# Lipo_LiFePO4_Charger_2022-02-16.net
KiCad netlist of a schematic drawn in Altium Designer
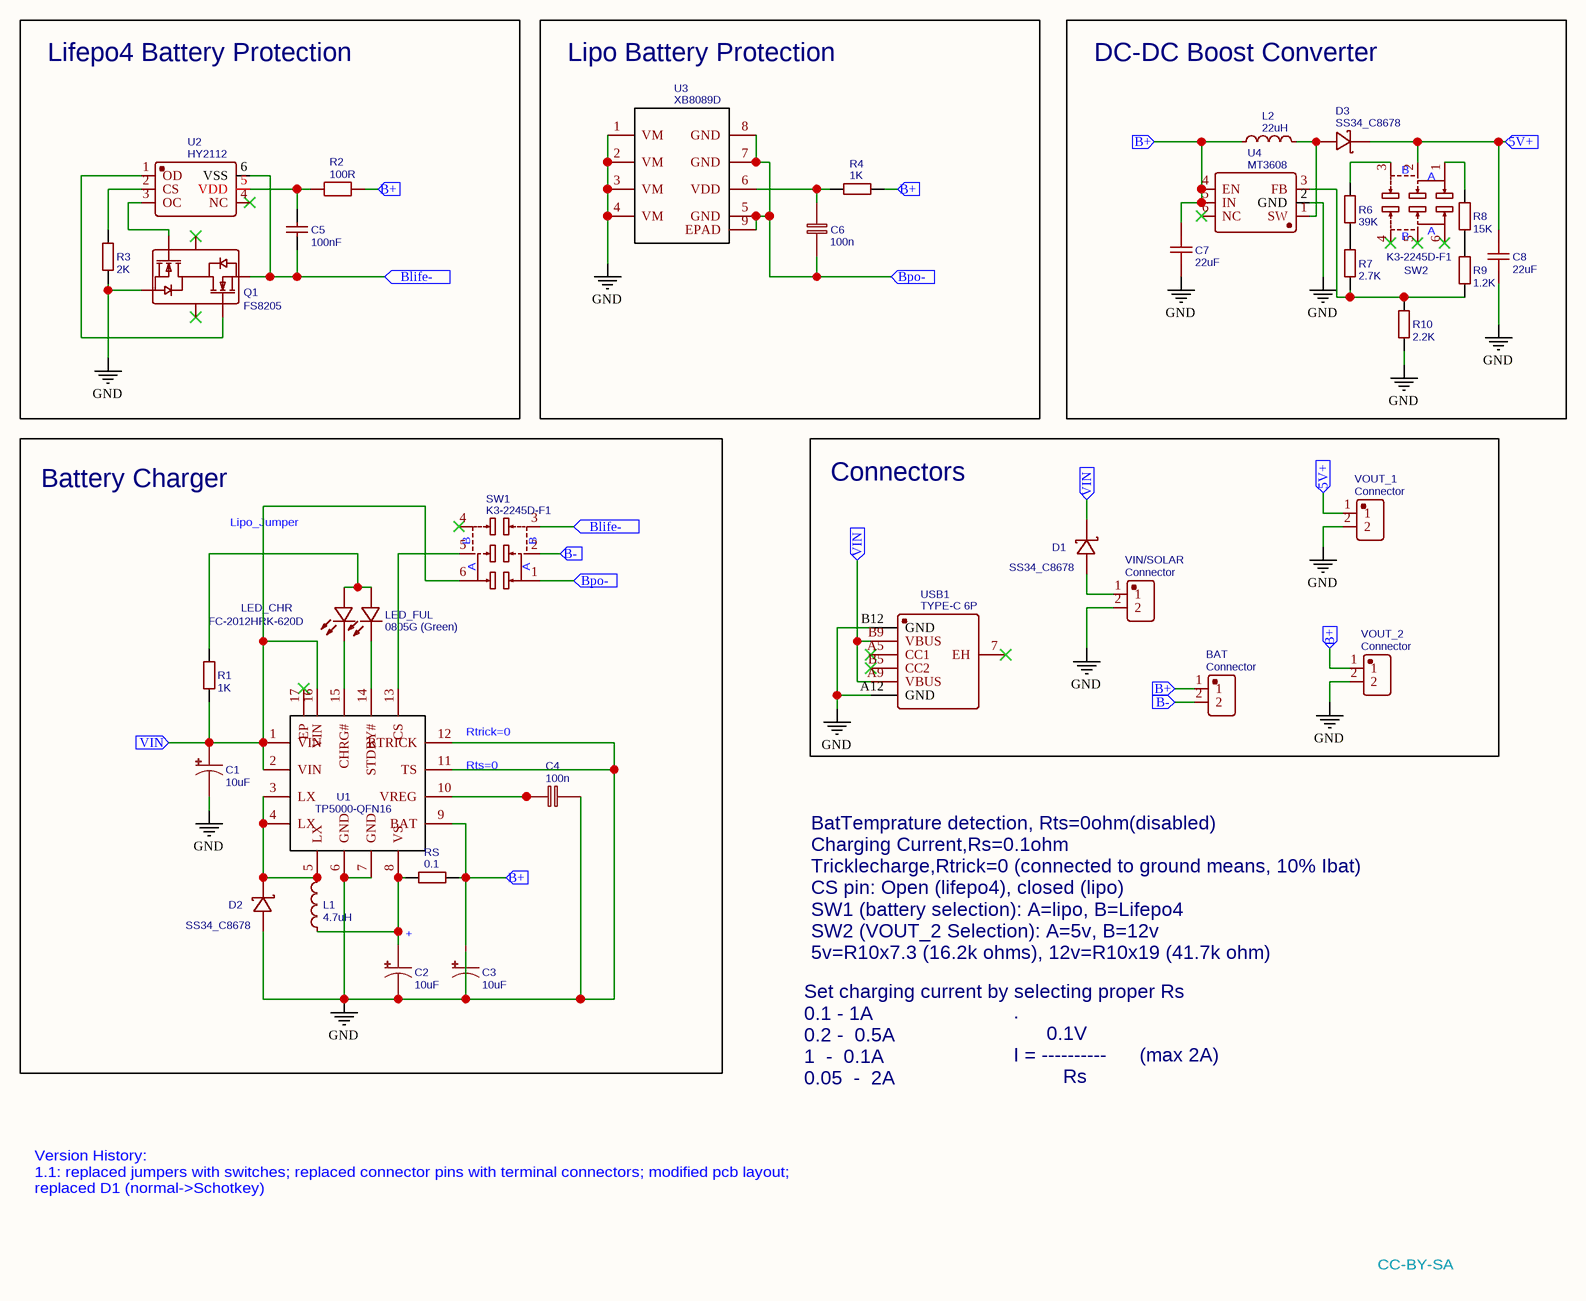
[diagram p0: Lipo_LiFePO4 Charger_2022-02-16.schdoc]

(export (version "E")
  (design (tool "Eeschema 10.0.6"))
  (components
    (comp (ref "BAT")
      (value "Connector")
      (fields
        (field (name "BOM_SUPPLIER PART") "C557685")
        (field (name "BOM_MANUFACTURER PART") "XY308-2.54-2P")
        (field (name "CONTRIBUTOR") "LCSC")
      )
      (libsource (lib "altium-import") (part "root_0_Connector_"))
    )
    (comp (ref "C1")
      (value "10uF")
      (fields
        (field (name "BOM_MANUFACTURER PART") "293D106X9020B2TE3")
        (field (name "BOM_SUPPLIER PART") "C180482")
        (field (name "CONTRIBUTOR") "LCSC")
      )
      (libsource (lib "altium-import") (part "root_1_10uF_"))
    )
    (comp (ref "C2")
      (value "10uF")
      (fields
        (field (name "BOM_MANUFACTURER PART") "293D106X9020B2TE3")
        (field (name "BOM_SUPPLIER PART") "C180482")
        (field (name "CONTRIBUTOR") "LCSC")
      )
      (libsource (lib "altium-import") (part "root_1_10uF_"))
    )
    (comp (ref "C3")
      (value "10uF")
      (fields
        (field (name "BOM_MANUFACTURER PART") "293D106X9020B2TE3")
        (field (name "BOM_SUPPLIER PART") "C180482")
        (field (name "CONTRIBUTOR") "LCSC")
      )
      (libsource (lib "altium-import") (part "root_1_10uF_"))
    )
    (comp (ref "C4")
      (value "100n")
      (fields
        (field (name "BOM_MANUFACTURER PART") "CC0805KRX7R9BB104")
        (field (name "BOM_SUPPLIER PART") "C49678")
      )
      (libsource (lib "altium-import") (part "root_1_100n_"))
    )
    (comp (ref "C5")
      (value "100nF")
      (fields
        (field (name "BOM_MANUFACTURER PART") "CC0805KRX7R9BB104")
        (field (name "BOM_SUPPLIER PART") "C49678")
      )
      (libsource (lib "altium-import") (part "root_1_100nF_"))
    )
    (comp (ref "C6")
      (value "100n")
      (fields
        (field (name "BOM_MANUFACTURER PART") "CC0805KRX7R9BB104")
        (field (name "BOM_SUPPLIER PART") "C49678")
      )
      (libsource (lib "altium-import") (part "root_0_100n_"))
    )
    (comp (ref "C7")
      (value "22uF")
      (fields
        (field (name "BOM_MANUFACTURER PART") "CL21A226MAQNNNE")
        (field (name "BOM_SUPPLIER PART") "C45783")
      )
      (libsource (lib "altium-import") (part "root_1_22uF_"))
    )
    (comp (ref "C8")
      (value "22uF")
      (fields
        (field (name "BOM_MANUFACTURER PART") "CL21A226MAQNNNE")
        (field (name "BOM_SUPPLIER PART") "C45783")
      )
      (libsource (lib "altium-import") (part "root_1_22uF_"))
    )
    (comp (ref "D1")
      (value "SS34_C8678")
      (fields (field (name "BOM_MANUFACTURER PART") "SS34") (field (name "BOM_SUPPLIER PART") "C8678"))
      (libsource (lib "altium-import") (part "root_3_SS34_C8678_"))
    )
    (comp (ref "D2")
      (value "SS34_C8678")
      (fields (field (name "BOM_MANUFACTURER PART") "SS34") (field (name "BOM_SUPPLIER PART") "C8678"))
      (libsource (lib "altium-import") (part "root_3_SS34_C8678_"))
    )
    (comp (ref "D3")
      (value "SS34_C8678")
      (fields (field (name "BOM_MANUFACTURER PART") "SS34") (field (name "BOM_SUPPLIER PART") "C8678"))
      (libsource (lib "altium-import") (part "root_2_SS34_C8678_"))
    )
    (comp (ref "L1")
      (value "4.7uH")
      (fields
        (field (name "BOM_MANUFACTURER PART") "SMMS0650-4R7M")
        (field (name "BOM_SUPPLIER PART") "C149582")
      )
      (libsource (lib "altium-import") (part "root_1_4.7uH_"))
    )
    (comp (ref "L2")
      (value "22uH")
      (fields
        (field (name "BOM_MANUFACTURER PART") "SMRH74-220MT")
        (field (name "BOM_SUPPLIER PART") "C27442")
      )
      (libsource (lib "altium-import") (part "root_0_22uH_"))
    )
    (comp (ref "LED_CHR")
      (value "FC-2012HRK-620D")
      (fields (field (name "BOM_SUPPLIER PART") "C84256"))
      (libsource (lib "altium-import") (part "root_1_FC-2012HRK-620D_"))
    )
    (comp (ref "LED_FUL")
      (value "0805G (Green)")
      (fields (field (name "BOM_SUPPLIER PART") "C2297"))
      (libsource (lib "altium-import") (part "root_1_0805G (Green)_"))
    )
    (comp (ref "Q1")
      (value "FS8205")
      (fields (field (name "BOM_SUPPLIER PART") "C32254"))
      (libsource (lib "altium-import") (part "root_2_FS8205_"))
    )
    (comp (ref "R1")
      (value "1K")
      (fields
        (field (name "BOM_MANUFACTURER PART") "0805W8F1001T5E")
        (field (name "BOM_SUPPLIER PART") "C17513")
      )
      (libsource (lib "altium-import") (part "root_1_1K_"))
    )
    (comp (ref "R2")
      (value "100R")
      (fields
        (field (name "BOM_MANUFACTURER PART") "0805W8F1000T5E")
        (field (name "BOM_SUPPLIER PART") "C17408")
      )
      (libsource (lib "altium-import") (part "root_0_100R_"))
    )
    (comp (ref "R3")
      (value "2K")
      (fields
        (field (name "BOM_MANUFACTURER PART") "0805W8F2001T5E")
        (field (name "BOM_SUPPLIER PART") "C17604")
      )
      (libsource (lib "altium-import") (part "root_1_2K_"))
    )
    (comp (ref "R4")
      (value "1K")
      (fields
        (field (name "BOM_MANUFACTURER PART") "0805W8F1001T5E")
        (field (name "BOM_SUPPLIER PART") "C17513")
      )
      (libsource (lib "altium-import") (part "root_2_1K_"))
    )
    (comp (ref "R6")
      (value "39K")
      (fields
        (field (name "BOM_MANUFACTURER PART") "0805W8F3902T5E")
        (field (name "BOM_SUPPLIER PART") "C25826")
      )
      (libsource (lib "altium-import") (part "root_1_39K_"))
    )
    (comp (ref "R7")
      (value "2.7K")
      (fields
        (field (name "BOM_MANUFACTURER PART") "0805W8F2701T5E")
        (field (name "BOM_SUPPLIER PART") "C17530")
      )
      (libsource (lib "altium-import") (part "root_1_2.7K_"))
    )
    (comp (ref "R8")
      (value "15K")
      (fields
        (field (name "BOM_MANUFACTURER PART") "0805W8F1502T5E")
        (field (name "BOM_SUPPLIER PART") "C17475")
      )
      (libsource (lib "altium-import") (part "root_1_15K_"))
    )
    (comp (ref "R9")
      (value "1.2K")
      (fields
        (field (name "BOM_MANUFACTURER PART") "0805W8F1201T5E")
        (field (name "BOM_SUPPLIER PART") "C17379")
      )
      (libsource (lib "altium-import") (part "root_1_1.2K_"))
    )
    (comp (ref "R10")
      (value "2.2K")
      (fields
        (field (name "BOM_MANUFACTURER PART") "0805W8F2201T5E")
        (field (name "BOM_SUPPLIER PART") "C17520")
      )
      (libsource (lib "altium-import") (part "root_1_2.2K_"))
    )
    (comp (ref "RS")
      (value "0.1")
      (fields
        (field (name "BOM_MANUFACTURER PART") "1206W4F100LT5E")
        (field (name "BOM_SUPPLIER PART") "C25334")
      )
      (libsource (lib "altium-import") (part "root_0_0.1_"))
    )
    (comp (ref "SW1")
      (value "K3-2245D-F1")
      (fields (field (name "BOM_SUPPLIER PART") "C223863") (field (name "CONTRIBUTOR") "LCSC"))
      (libsource (lib "altium-import") (part "root_1_K3-2245D-F1_"))
    )
    (comp (ref "SW2")
      (value "K3-2245D-F1")
      (fields (field (name "BOM_SUPPLIER PART") "C223863") (field (name "CONTRIBUTOR") "LCSC"))
      (libsource (lib "altium-import") (part "root_2_K3-2245D-F1_"))
    )
    (comp (ref "U1")
      (value "TP5000-QFN16")
      (fields (field (name "BOM_SUPPLIER PART") "C51699"))
      (libsource (lib "altium-import") (part "root_0_TP5000-QFN16_"))
    )
    (comp (ref "U2")
      (value "HY2112")
      (fields (field (name "BOM_SUPPLIER PART") "C161942") (field (name "CONTRIBUTOR") "LCSC"))
      (libsource (lib "altium-import") (part "root_0_HY2112_"))
    )
    (comp (ref "U3")
      (value "XB8089D")
      (fields (field (name "BOM_SUPPLIER PART") "C79928"))
      (libsource (lib "altium-import") (part "root_0_XB8089D_"))
    )
    (comp (ref "U4")
      (value "MT3608")
      (fields (field (name "BOM_SUPPLIER PART") "C84817"))
      (libsource (lib "altium-import") (part "root_2_MT3608_"))
    )
    (comp (ref "USB1")
      (value "TYPE-C 6P")
      (fields (field (name "BOM_SUPPLIER PART") "C456012") (field (name "CONTRIBUTOR") "LCSC"))
      (libsource (lib "altium-import") (part "root_0_TYPE-C 6P_"))
    )
    (comp (ref "VIN/SOLAR")
      (value "Connector")
      (fields
        (field (name "BOM_SUPPLIER PART") "C557685")
        (field (name "BOM_MANUFACTURER PART") "XY308-2.54-2P")
        (field (name "CONTRIBUTOR") "LCSC")
      )
      (libsource (lib "altium-import") (part "root_0_Connector_"))
    )
    (comp (ref "VOUT_1")
      (value "Connector")
      (fields
        (field (name "BOM_SUPPLIER PART") "C557685")
        (field (name "BOM_MANUFACTURER PART") "XY308-2.54-2P")
        (field (name "CONTRIBUTOR") "LCSC")
      )
      (libsource (lib "altium-import") (part "root_0_Connector_"))
    )
    (comp (ref "VOUT_2")
      (value "Connector")
      (fields
        (field (name "BOM_SUPPLIER PART") "C557685")
        (field (name "BOM_MANUFACTURER PART") "XY308-2.54-2P")
        (field (name "CONTRIBUTOR") "LCSC")
      )
      (libsource (lib "altium-import") (part "root_0_Connector_"))
    )
  )
  (nets
    (net (code "1") (name "/5V+") (class "Default")
      (node (ref "C8") (pin "2") (pinfunction "2_2") (pintype "passive"))
      (node (ref "D3") (pin "1") (pinfunction "K_1") (pintype "passive"))
      (node (ref "SW2") (pin "2") (pinfunction "2_2") (pintype "passive"))
      (node (ref "VOUT_1") (pin "1") (pinfunction "1_1") (pintype "passive"))
    )
    (net (code "2") (name "/B+") (class "Default")
      (node (ref "BAT") (pin "1") (pinfunction "1_1") (pintype "passive"))
      (node (ref "C3") (pin "1") (pinfunction "1_1") (pintype "passive"))
      (node (ref "C7") (pin "2") (pinfunction "2_2") (pintype "passive"))
      (node (ref "L2") (pin "1") (pinfunction "1_1") (pintype "passive"))
      (node (ref "R2") (pin "2") (pinfunction "2_2") (pintype "passive"))
      (node (ref "R4") (pin "1") (pinfunction "1_1") (pintype "passive"))
      (node (ref "RS") (pin "2") (pinfunction "2_2") (pintype "passive"))
      (node (ref "U1") (pin "9") (pinfunction "BAT_9") (pintype "passive"))
      (node (ref "U4") (pin "4") (pinfunction "EN_4") (pintype "passive"))
      (node (ref "U4") (pin "5") (pinfunction "IN_5") (pintype "passive"))
      (node (ref "VOUT_2") (pin "1") (pinfunction "1_1") (pintype "passive"))
    )
    (net (code "3") (name "/B-") (class "Default")
      (node (ref "BAT") (pin "2") (pinfunction "2_2") (pintype "passive"))
      (node (ref "SW1") (pin "2") (pinfunction "2_2") (pintype "passive"))
    )
    (net (code "4") (name "/Blife-") (class "Default")
      (node (ref "C5") (pin "1") (pinfunction "1_1") (pintype "passive"))
      (node (ref "Q1") (pin "1") (pinfunction "S1_1") (pintype "passive"))
      (node (ref "SW1") (pin "3") (pinfunction "3_3") (pintype "passive"))
      (node (ref "U2") (pin "6") (pinfunction "VSS_6") (pintype "passive"))
    )
    (net (code "5") (name "/Bpo-") (class "Default")
      (node (ref "C6") (pin "2") (pinfunction "2_2") (pintype "passive"))
      (node (ref "SW1") (pin "1") (pinfunction "1_1") (pintype "passive"))
      (node (ref "U3") (pin "5") (pinfunction "GND_5") (pintype "passive"))
      (node (ref "U3") (pin "7") (pinfunction "GND_7") (pintype "passive"))
      (node (ref "U3") (pin "8") (pinfunction "GND_8") (pintype "passive"))
      (node (ref "U3") (pin "9") (pinfunction "EPAD_9") (pintype "passive"))
    )
    (net (code "6") (name "/VIN") (class "Default")
      (node (ref "C1") (pin "1") (pinfunction "1_1") (pintype "passive"))
      (node (ref "D1") (pin "1") (pinfunction "K_1") (pintype "passive"))
      (node (ref "R1") (pin "1") (pinfunction "1_1") (pintype "passive"))
      (node (ref "SW1") (pin "6") (pinfunction "6_6") (pintype "passive"))
      (node (ref "U1") (pin "1") (pinfunction "VIN_1") (pintype "passive"))
      (node (ref "U1") (pin "16") (pinfunction "VIN_16") (pintype "passive"))
      (node (ref "U1") (pin "2") (pinfunction "VIN_2") (pintype "passive"))
      (node (ref "USB1") (pin "A9") (pinfunction "VBUS_A9") (pintype "passive"))
      (node (ref "USB1") (pin "B9") (pinfunction "VBUS_B9") (pintype "passive"))
    )
    (net (code "7") (name "GND") (class "Default")
      (node (ref "C1") (pin "2") (pinfunction "2_2") (pintype "passive"))
      (node (ref "C2") (pin "2") (pinfunction "2_2") (pintype "passive"))
      (node (ref "C3") (pin "2") (pinfunction "2_2") (pintype "passive"))
      (node (ref "C4") (pin "2") (pinfunction "2_2") (pintype "passive"))
      (node (ref "C7") (pin "1") (pinfunction "1_1") (pintype "passive"))
      (node (ref "C8") (pin "1") (pinfunction "1_1") (pintype "passive"))
      (node (ref "D2") (pin "2") (pinfunction "A_2") (pintype "passive"))
      (node (ref "Q1") (pin "3") (pinfunction "S2_3") (pintype "passive"))
      (node (ref "R10") (pin "1") (pinfunction "1_1") (pintype "passive"))
      (node (ref "R3") (pin "1") (pinfunction "1_1") (pintype "passive"))
      (node (ref "U1") (pin "11") (pinfunction "TS_11") (pintype "passive"))
      (node (ref "U1") (pin "12") (pinfunction "RTRICK_12") (pintype "passive"))
      (node (ref "U1") (pin "6") (pinfunction "GND_6") (pintype "passive"))
      (node (ref "U1") (pin "7") (pinfunction "GND_7") (pintype "passive"))
      (node (ref "U3") (pin "1") (pinfunction "VM_1") (pintype "passive"))
      (node (ref "U3") (pin "2") (pinfunction "VM_2") (pintype "passive"))
      (node (ref "U3") (pin "3") (pinfunction "VM_3") (pintype "passive"))
      (node (ref "U3") (pin "4") (pinfunction "VM_4") (pintype "passive"))
      (node (ref "U4") (pin "2") (pinfunction "GND_2") (pintype "passive"))
      (node (ref "USB1") (pin "A12") (pinfunction "GND_A12") (pintype "passive"))
      (node (ref "USB1") (pin "B12") (pinfunction "GND_B12") (pintype "passive"))
      (node (ref "VIN/SOLAR") (pin "2") (pinfunction "2_2") (pintype "passive"))
      (node (ref "VOUT_1") (pin "2") (pinfunction "2_2") (pintype "passive"))
      (node (ref "VOUT_2") (pin "2") (pinfunction "2_2") (pintype "passive"))
    )
    (net (code "8") (name "Net-(D1-A)") (class "Default")
      (node (ref "D1") (pin "2") (pinfunction "A_2") (pintype "passive"))
      (node (ref "VIN/SOLAR") (pin "1") (pinfunction "1_1") (pintype "passive"))
    )
    (net (code "9") (name "Net-(D2-K)") (class "Default")
      (node (ref "D2") (pin "1") (pinfunction "K_1") (pintype "passive"))
      (node (ref "L1") (pin "2") (pinfunction "2_2") (pintype "passive"))
      (node (ref "U1") (pin "3") (pinfunction "LX_3") (pintype "passive"))
      (node (ref "U1") (pin "4") (pinfunction "LX_4") (pintype "passive"))
      (node (ref "U1") (pin "5") (pinfunction "LX_5") (pintype "passive"))
    )
    (net (code "10") (name "Net-(D3-A)") (class "Default")
      (node (ref "D3") (pin "2") (pinfunction "A_2") (pintype "passive"))
      (node (ref "L2") (pin "2") (pinfunction "2_2") (pintype "passive"))
      (node (ref "U4") (pin "1") (pinfunction "SW_1") (pintype "passive"))
    )
    (net (code "11") (name "Net-(LED_CHR-+)") (class "Default")
      (node (ref "LED_CHR") (pin "2") (pinfunction "+_2") (pintype "passive"))
      (node (ref "LED_FUL") (pin "2") (pinfunction "A_2") (pintype "passive"))
      (node (ref "R1") (pin "2") (pinfunction "2_2") (pintype "passive"))
    )
    (net (code "12") (name "Net-(LED_CHR--)") (class "Default")
      (node (ref "LED_CHR") (pin "1") (pinfunction "-_1") (pintype "passive"))
      (node (ref "U1") (pin "15") (pinfunction "CHRG#_15") (pintype "passive"))
    )
    (net (code "13") (name "Net-(LED_FUL-K)") (class "Default")
      (node (ref "LED_FUL") (pin "1") (pinfunction "K_1") (pintype "passive"))
      (node (ref "U1") (pin "14") (pinfunction "STDBY#_14") (pintype "passive"))
    )
    (net (code "14") (name "Net-(Q1-G1)") (class "Default")
      (node (ref "Q1") (pin "6") (pinfunction "G1_6") (pintype "passive"))
      (node (ref "U2") (pin "1") (pinfunction "OD_1") (pintype "passive"))
    )
    (net (code "15") (name "Net-(Q1-G2)") (class "Default")
      (node (ref "Q1") (pin "4") (pinfunction "G2_4") (pintype "passive"))
      (node (ref "U2") (pin "3") (pinfunction "OC_3") (pintype "passive"))
    )
    (net (code "16") (name "Net-(R6-Pad1)") (class "Default")
      (node (ref "R6") (pin "1") (pinfunction "1_1") (pintype "passive"))
      (node (ref "R7") (pin "2") (pinfunction "2_2") (pintype "passive"))
    )
    (net (code "17") (name "Net-(R6-Pad2)") (class "Default")
      (node (ref "R6") (pin "2") (pinfunction "2_2") (pintype "passive"))
      (node (ref "SW2") (pin "3") (pinfunction "3_3") (pintype "passive"))
    )
    (net (code "18") (name "Net-(R8-Pad1)") (class "Default")
      (node (ref "R8") (pin "1") (pinfunction "1_1") (pintype "passive"))
      (node (ref "R9") (pin "2") (pinfunction "2_2") (pintype "passive"))
    )
    (net (code "19") (name "Net-(R8-Pad2)") (class "Default")
      (node (ref "R8") (pin "2") (pinfunction "2_2") (pintype "passive"))
      (node (ref "SW2") (pin "1") (pinfunction "1_1") (pintype "passive"))
    )
    (net (code "20") (name "Net-(U1-CS)") (class "Default")
      (node (ref "SW1") (pin "5") (pinfunction "5_5") (pintype "passive"))
      (node (ref "U1") (pin "13") (pinfunction "CS_13") (pintype "passive"))
    )
    (net (code "21") (name "Net-(U1-VREG)") (class "Default")
      (node (ref "C4") (pin "1") (pinfunction "1_1") (pintype "passive"))
      (node (ref "U1") (pin "10") (pinfunction "VREG_10") (pintype "passive"))
    )
    (net (code "22") (name "Net-(U1-VS)") (class "Default")
      (node (ref "C2") (pin "1") (pinfunction "1_1") (pintype "passive"))
      (node (ref "L1") (pin "1") (pinfunction "1_1") (pintype "passive"))
      (node (ref "RS") (pin "1") (pinfunction "1_1") (pintype "passive"))
      (node (ref "U1") (pin "8") (pinfunction "VS_8") (pintype "passive"))
    )
    (net (code "23") (name "Net-(U2-CS)") (class "Default")
      (node (ref "R3") (pin "2") (pinfunction "2_2") (pintype "passive"))
      (node (ref "U2") (pin "2") (pinfunction "CS_2") (pintype "passive"))
    )
    (net (code "24") (name "Net-(U2-VDD)") (class "Default")
      (node (ref "C5") (pin "2") (pinfunction "2_2") (pintype "passive"))
      (node (ref "R2") (pin "1") (pinfunction "1_1") (pintype "passive"))
      (node (ref "U2") (pin "5") (pinfunction "VDD_5") (pintype "passive"))
    )
    (net (code "25") (name "Net-(U3-VDD)") (class "Default")
      (node (ref "C6") (pin "1") (pinfunction "1_1") (pintype "passive"))
      (node (ref "R4") (pin "2") (pinfunction "2_2") (pintype "passive"))
      (node (ref "U3") (pin "6") (pinfunction "VDD_6") (pintype "passive"))
    )
    (net (code "26") (name "Net-(U4-FB)") (class "Default")
      (node (ref "R10") (pin "2") (pinfunction "2_2") (pintype "passive"))
      (node (ref "R7") (pin "1") (pinfunction "1_1") (pintype "passive"))
      (node (ref "R9") (pin "1") (pinfunction "1_1") (pintype "passive"))
      (node (ref "U4") (pin "3") (pinfunction "FB_3") (pintype "passive"))
    )
    (net (code "27") (name "unconnected-(Q1-D12-Pad2)") (class "Default")
      (node (ref "Q1") (pin "2") (pinfunction "D12_2") (pintype "passive+no_connect"))
    )
    (net (code "28") (name "unconnected-(Q1-D12-Pad5)") (class "Default")
      (node (ref "Q1") (pin "5") (pinfunction "D12_5") (pintype "passive+no_connect"))
    )
    (net (code "29") (name "unconnected-(SW1-Pad4)") (class "Default")
      (node (ref "SW1") (pin "4") (pinfunction "4_4") (pintype "passive+no_connect"))
    )
    (net (code "30") (name "unconnected-(SW2-Pad4)") (class "Default")
      (node (ref "SW2") (pin "4") (pinfunction "4_4") (pintype "passive+no_connect"))
    )
    (net (code "31") (name "unconnected-(SW2-Pad5)") (class "Default")
      (node (ref "SW2") (pin "5") (pinfunction "5_5") (pintype "passive+no_connect"))
    )
    (net (code "32") (name "unconnected-(SW2-Pad6)") (class "Default")
      (node (ref "SW2") (pin "6") (pinfunction "6_6") (pintype "passive+no_connect"))
    )
    (net (code "33") (name "unconnected-(U1-EP-Pad17)") (class "Default")
      (node (ref "U1") (pin "17") (pinfunction "EP_17") (pintype "passive+no_connect"))
    )
    (net (code "34") (name "unconnected-(U2-NC-Pad4)") (class "Default")
      (node (ref "U2") (pin "4") (pinfunction "NC_4") (pintype "passive+no_connect"))
    )
    (net (code "35") (name "unconnected-(U4-NC-Pad6)") (class "Default")
      (node (ref "U4") (pin "6") (pinfunction "NC_6") (pintype "passive+no_connect"))
    )
    (net (code "36") (name "unconnected-(USB1-CC1-PadA5)") (class "Default")
      (node (ref "USB1") (pin "A5") (pinfunction "CC1_A5") (pintype "passive+no_connect"))
    )
    (net (code "37") (name "unconnected-(USB1-CC2-PadB5)") (class "Default")
      (node (ref "USB1") (pin "B5") (pinfunction "CC2_B5") (pintype "passive+no_connect"))
    )
    (net (code "38") (name "unconnected-(USB1-EH-Pad7)") (class "Default")
      (node (ref "USB1") (pin "7") (pinfunction "EH_7") (pintype "passive+no_connect"))
    )
  )
)
